# berthaBluetooth.net
KiCad netlist of a schematic drawn in EAGLE
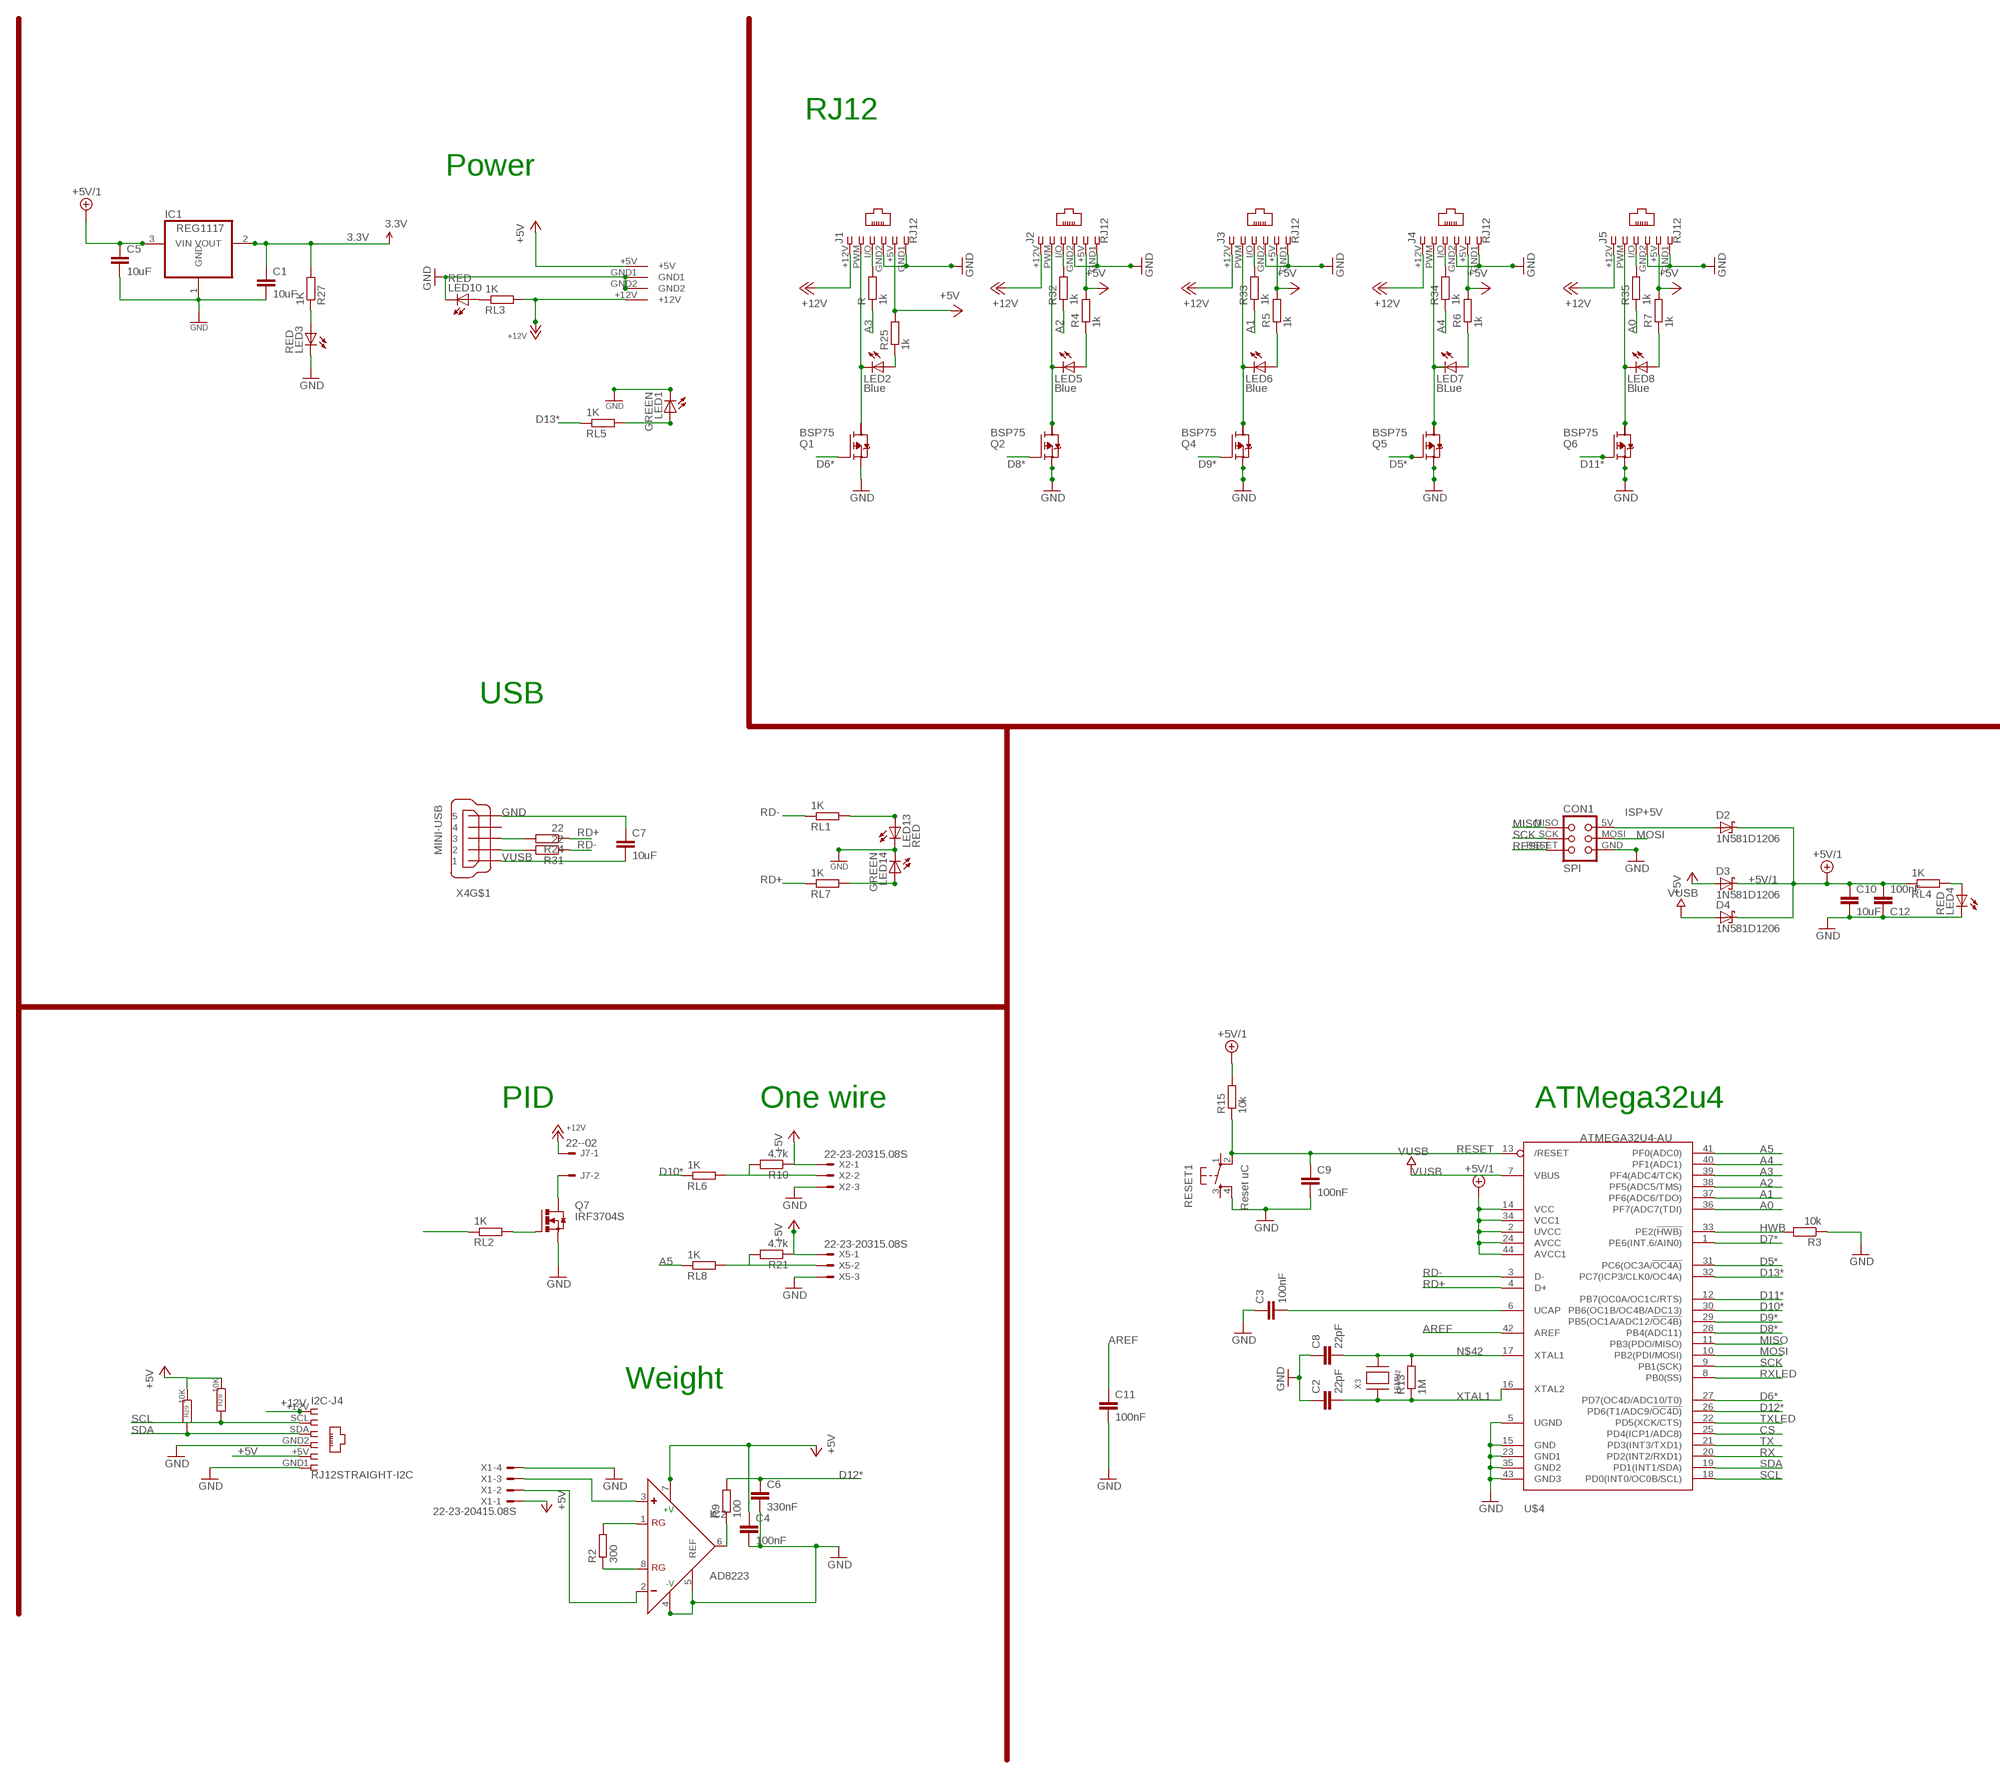
[diagram p0: schematic, sheet 1, part 1 of 2]
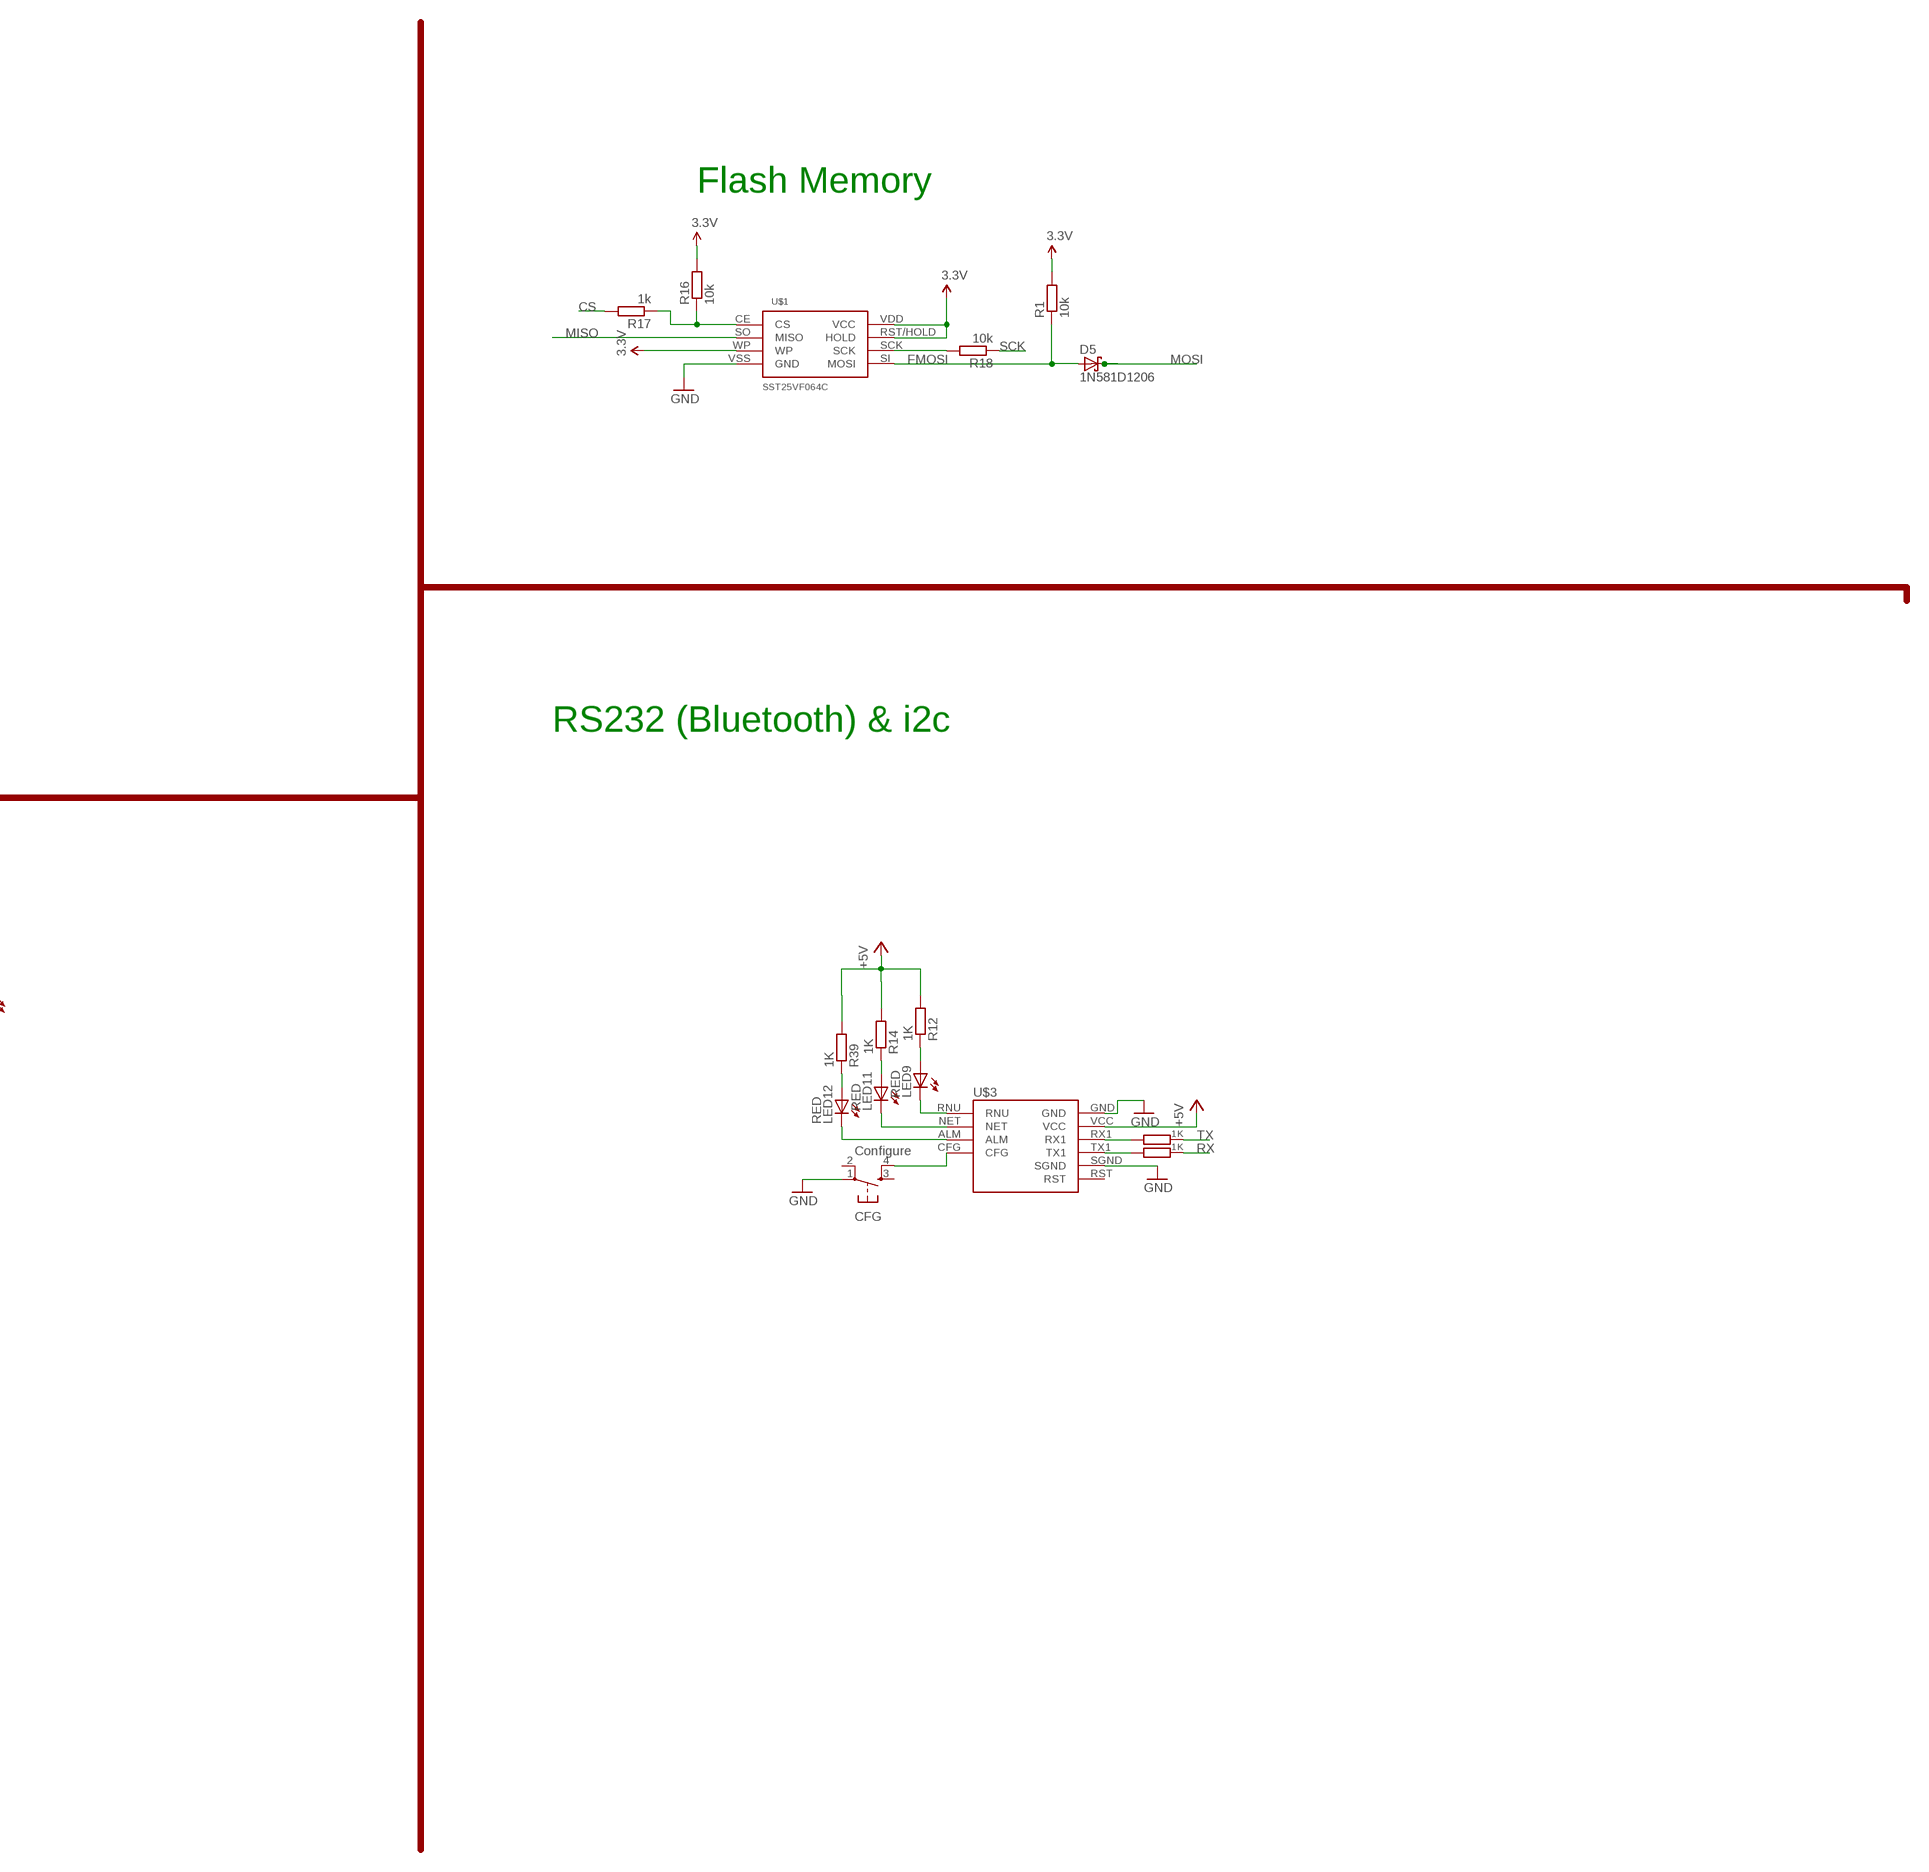
[diagram p1: schematic, sheet 1, part 2 of 2]

(export (version "E")
  (design (tool "Eeschema 10.0.6"))
  (components
    (comp (ref "C1")
      (value "10uF")
      (footprint "eagle-import:C1206")
      (libsource (lib "eagle-import") (part "C-EUC1206"))
    )
    (comp (ref "C2")
      (value "22pF")
      (footprint "eagle-import:C1206")
      (libsource (lib "eagle-import") (part "C-EUC1206"))
    )
    (comp (ref "C3")
      (value "100nF")
      (footprint "eagle-import:C1206")
      (libsource (lib "eagle-import") (part "C-EUC1206"))
    )
    (comp (ref "C4")
      (value "100nF")
      (footprint "eagle-import:C1206")
      (libsource (lib "eagle-import") (part "C-EUC1206"))
    )
    (comp (ref "C5")
      (value "10uF")
      (footprint "eagle-import:C1206")
      (libsource (lib "eagle-import") (part "C-EUC1206"))
    )
    (comp (ref "C6")
      (value "330nF")
      (footprint "eagle-import:C1206")
      (libsource (lib "eagle-import") (part "C-EUC1206"))
    )
    (comp (ref "C7")
      (value "10uF")
      (footprint "eagle-import:C1206")
      (libsource (lib "eagle-import") (part "C-EUC1206"))
    )
    (comp (ref "C8")
      (value "22pF")
      (footprint "eagle-import:C1206")
      (libsource (lib "eagle-import") (part "C-EUC1206"))
    )
    (comp (ref "C9")
      (value "100nF")
      (footprint "eagle-import:C1206")
      (libsource (lib "eagle-import") (part "C-EUC1206"))
    )
    (comp (ref "C10")
      (value "10uF")
      (footprint "eagle-import:C1206")
      (libsource (lib "eagle-import") (part "C-EUC1206"))
    )
    (comp (ref "C11")
      (value "100nF")
      (footprint "eagle-import:C1206")
      (libsource (lib "eagle-import") (part "C-EUC1206"))
    )
    (comp (ref "C12")
      (value "100nF")
      (footprint "eagle-import:C1206")
      (libsource (lib "eagle-import") (part "C-EUC1206"))
    )
    (comp (ref "CFG")
      (value "Configure")
      (footprint "eagle-import:TACTILE_SWITCH_SMD")
      (libsource (lib "eagle-import") (part "TAC_SWITCHSMD"))
    )
    (comp (ref "CON1")
      (value "SPI")
      (footprint "eagle-import:TC2030-MCP-NL")
      (libsource (lib "eagle-import") (part "TINYISPT"))
    )
    (comp (ref "D2")
      (value "1N581D1206")
      (footprint "eagle-import:LED-1206")
      (libsource (lib "eagle-import") (part "1N581D1206"))
    )
    (comp (ref "D3")
      (value "1N581D1206")
      (footprint "eagle-import:LED-1206")
      (libsource (lib "eagle-import") (part "1N581D1206"))
    )
    (comp (ref "D4")
      (value "1N581D1206")
      (footprint "eagle-import:LED-1206")
      (libsource (lib "eagle-import") (part "1N581D1206"))
    )
    (comp (ref "D5")
      (value "1N581D1206")
      (footprint "eagle-import:LED-1206")
      (libsource (lib "eagle-import") (part "1N581D1206"))
    )
    (comp (ref "I2C-J4")
      (value "RJ12STRAIGHT-I2C")
      (footprint "eagle-import:RJ12-STRAIGHT-I2C")
      (libsource (lib "eagle-import") (part "RJ12STRAIGHT-I2C"))
    )
    (comp (ref "IC1")
      (value "REG1117")
      (footprint "eagle-import:SOT223")
      (libsource (lib "eagle-import") (part "REG1117"))
    )
    (comp (ref "IC2")
      (value "AD8223")
      (footprint "eagle-import:SO8")
      (fields (field (name "MPN") "AD620AR"))
      (libsource (lib "eagle-import") (part "AD620R"))
    )
    (comp (ref "J1")
      (value "RJ12")
      (footprint "eagle-import:RJ12-STRAIGHT")
      (libsource (lib "eagle-import") (part "RJ12STRAIGHT"))
    )
    (comp (ref "J2")
      (value "RJ12")
      (footprint "eagle-import:RJ12-STRAIGHT")
      (libsource (lib "eagle-import") (part "RJ12STRAIGHT"))
    )
    (comp (ref "J3")
      (value "RJ12")
      (footprint "eagle-import:RJ12-STRAIGHT")
      (libsource (lib "eagle-import") (part "RJ12STRAIGHT"))
    )
    (comp (ref "J4")
      (value "RJ12")
      (footprint "eagle-import:RJ12-STRAIGHT")
      (libsource (lib "eagle-import") (part "RJ12STRAIGHT"))
    )
    (comp (ref "J5")
      (value "RJ12")
      (footprint "eagle-import:RJ12-STRAIGHT")
      (libsource (lib "eagle-import") (part "RJ12STRAIGHT"))
    )
    (comp (ref "J7")
      (value "22--02")
      (footprint "eagle-import:2-PIN-5.08S")
      (libsource (lib "eagle-import") (part "22-?-02"))
    )
    (comp (ref "LED1")
      (value "GREEN")
      (footprint "eagle-import:CHIPLED_1206")
      (libsource (lib "eagle-import") (part "LEDCHIPLED_1206"))
    )
    (comp (ref "LED2")
      (value "Blue")
      (footprint "eagle-import:CHIPLED_1206")
      (libsource (lib "eagle-import") (part "LEDCHIPLED_1206"))
    )
    (comp (ref "LED3")
      (value "RED")
      (footprint "eagle-import:CHIPLED_1206")
      (libsource (lib "eagle-import") (part "LEDCHIPLED_1206"))
    )
    (comp (ref "LED4")
      (value "RED")
      (footprint "eagle-import:CHIPLED_1206")
      (libsource (lib "eagle-import") (part "LEDCHIPLED_1206"))
    )
    (comp (ref "LED5")
      (value "Blue")
      (footprint "eagle-import:CHIPLED_1206")
      (libsource (lib "eagle-import") (part "LEDCHIPLED_1206"))
    )
    (comp (ref "LED6")
      (value "Blue")
      (footprint "eagle-import:CHIPLED_1206")
      (libsource (lib "eagle-import") (part "LEDCHIPLED_1206"))
    )
    (comp (ref "LED7")
      (value "BLue")
      (footprint "eagle-import:CHIPLED_1206")
      (libsource (lib "eagle-import") (part "LEDCHIPLED_1206"))
    )
    (comp (ref "LED8")
      (value "Blue")
      (footprint "eagle-import:CHIPLED_1206")
      (libsource (lib "eagle-import") (part "LEDCHIPLED_1206"))
    )
    (comp (ref "LED9")
      (value "RED")
      (footprint "eagle-import:CHIPLED_1206")
      (libsource (lib "eagle-import") (part "LEDCHIPLED_1206"))
    )
    (comp (ref "LED10")
      (value "RED")
      (footprint "eagle-import:CHIPLED_1206")
      (libsource (lib "eagle-import") (part "LEDCHIPLED_1206"))
    )
    (comp (ref "LED11")
      (value "RED")
      (footprint "eagle-import:CHIPLED_1206")
      (libsource (lib "eagle-import") (part "LEDCHIPLED_1206"))
    )
    (comp (ref "LED12")
      (value "RED")
      (footprint "eagle-import:CHIPLED_1206")
      (libsource (lib "eagle-import") (part "LEDCHIPLED_1206"))
    )
    (comp (ref "LED13")
      (value "RED")
      (footprint "eagle-import:CHIPLED_1206")
      (libsource (lib "eagle-import") (part "LEDCHIPLED_1206"))
    )
    (comp (ref "LED14")
      (value "GREEN")
      (footprint "eagle-import:CHIPLED_1206")
      (libsource (lib "eagle-import") (part "LEDCHIPLED_1206"))
    )
    (comp (ref "Q1")
      (value "BSP75")
      (footprint "eagle-import:PG-SOT-223")
      (libsource (lib "eagle-import") (part "BSP613P"))
    )
    (comp (ref "Q2")
      (value "BSP75")
      (footprint "eagle-import:PG-SOT-223")
      (libsource (lib "eagle-import") (part "BSP613P"))
    )
    (comp (ref "Q4")
      (value "BSP75")
      (footprint "eagle-import:PG-SOT-223")
      (libsource (lib "eagle-import") (part "BSP613P"))
    )
    (comp (ref "Q5")
      (value "BSP75")
      (footprint "eagle-import:PG-SOT-223")
      (libsource (lib "eagle-import") (part "BSP613P"))
    )
    (comp (ref "Q6")
      (value "BSP75")
      (footprint "eagle-import:PG-SOT-223")
      (libsource (lib "eagle-import") (part "BSP613P"))
    )
    (comp (ref "Q7")
      (value "IRF3704S")
      (footprint "eagle-import:D2PACK")
      (libsource (lib "eagle-import") (part "IRF3704S"))
    )
    (comp (ref "R")
      (value "1k")
      (footprint "eagle-import:R0805")
      (libsource (lib "eagle-import") (part "R-EU_R0805"))
    )
    (comp (ref "R1")
      (value "10k")
      (footprint "eagle-import:R0805")
      (libsource (lib "eagle-import") (part "R-EU_R0805"))
    )
    (comp (ref "R2")
      (value "300")
      (footprint "eagle-import:R1206")
      (libsource (lib "eagle-import") (part "resistor_R-EU_R1206"))
    )
    (comp (ref "R3")
      (value "10k")
      (footprint "eagle-import:M0805")
      (libsource (lib "eagle-import") (part "resistor_R-EU_M0805"))
    )
    (comp (ref "R4")
      (value "1k")
      (footprint "eagle-import:R0805")
      (libsource (lib "eagle-import") (part "R-EU_R0805"))
    )
    (comp (ref "R5")
      (value "1k")
      (footprint "eagle-import:R0805")
      (libsource (lib "eagle-import") (part "R-EU_R0805"))
    )
    (comp (ref "R6")
      (value "1k")
      (footprint "eagle-import:R0805")
      (libsource (lib "eagle-import") (part "R-EU_R0805"))
    )
    (comp (ref "R7")
      (value "1k")
      (footprint "eagle-import:R0805")
      (libsource (lib "eagle-import") (part "R-EU_R0805"))
    )
    (comp (ref "R8")
      (value "1K")
      (footprint "eagle-import:R0805")
      (libsource (lib "eagle-import") (part "R-EU_R0805"))
    )
    (comp (ref "R9")
      (value "100")
      (footprint "eagle-import:R1206")
      (libsource (lib "eagle-import") (part "resistor_R-EU_R1206"))
    )
    (comp (ref "R10")
      (value "4.7k")
      (footprint "eagle-import:R1206")
      (libsource (lib "eagle-import") (part "resistor_R-EU_R1206"))
    )
    (comp (ref "R11")
      (value "1K")
      (footprint "eagle-import:R0805")
      (libsource (lib "eagle-import") (part "R-EU_R0805"))
    )
    (comp (ref "R12")
      (value "1K")
      (footprint "eagle-import:R0805")
      (libsource (lib "eagle-import") (part "R-EU_R0805"))
    )
    (comp (ref "R13")
      (value "1M")
      (footprint "eagle-import:R1206")
      (libsource (lib "eagle-import") (part "R-EU_R1206"))
    )
    (comp (ref "R14")
      (value "1K")
      (footprint "eagle-import:R0805")
      (libsource (lib "eagle-import") (part "R-EU_R0805"))
    )
    (comp (ref "R15")
      (value "10k")
      (footprint "eagle-import:M0805")
      (libsource (lib "eagle-import") (part "resistor_R-EU_M0805"))
    )
    (comp (ref "R16")
      (value "10k")
      (footprint "eagle-import:R0805")
      (libsource (lib "eagle-import") (part "R-EU_R0805"))
    )
    (comp (ref "R17")
      (value "1k")
      (footprint "eagle-import:R0805")
      (libsource (lib "eagle-import") (part "R-EU_R0805"))
    )
    (comp (ref "R18")
      (value "10k")
      (footprint "eagle-import:R0805")
      (libsource (lib "eagle-import") (part "R-EU_R0805"))
    )
    (comp (ref "R21")
      (value "4.7k")
      (footprint "eagle-import:R1206")
      (libsource (lib "eagle-import") (part "resistor_R-EU_R1206"))
    )
    (comp (ref "R24")
      (value "22")
      (footprint "eagle-import:M1206")
      (libsource (lib "eagle-import") (part "resistor_R-EU_M1206"))
    )
    (comp (ref "R25")
      (value "1k")
      (footprint "eagle-import:R0805")
      (libsource (lib "eagle-import") (part "R-EU_R0805"))
    )
    (comp (ref "R27")
      (value "1K")
      (footprint "eagle-import:R0805")
      (libsource (lib "eagle-import") (part "R-EU_R0805"))
    )
    (comp (ref "R28")
      (value "10K")
      (footprint "eagle-import:M0805")
      (libsource (lib "eagle-import") (part "resistor_R-EU_M0805"))
    )
    (comp (ref "R29")
      (value "10K")
      (footprint "eagle-import:M0805")
      (libsource (lib "eagle-import") (part "resistor_R-EU_M0805"))
    )
    (comp (ref "R31")
      (value "22")
      (footprint "eagle-import:M1206")
      (libsource (lib "eagle-import") (part "resistor_R-EU_M1206"))
    )
    (comp (ref "R32")
      (value "1k")
      (footprint "eagle-import:R0805")
      (libsource (lib "eagle-import") (part "R-EU_R0805"))
    )
    (comp (ref "R33")
      (value "1k")
      (footprint "eagle-import:R0805")
      (libsource (lib "eagle-import") (part "R-EU_R0805"))
    )
    (comp (ref "R34")
      (value "1k")
      (footprint "eagle-import:R0805")
      (libsource (lib "eagle-import") (part "R-EU_R0805"))
    )
    (comp (ref "R35")
      (value "1k")
      (footprint "eagle-import:R0805")
      (libsource (lib "eagle-import") (part "R-EU_R0805"))
    )
    (comp (ref "R39")
      (value "1K")
      (footprint "eagle-import:R0805")
      (libsource (lib "eagle-import") (part "R-EU_R0805"))
    )
    (comp (ref "RESET1")
      (value "Reset uC")
      (footprint "eagle-import:TACTILE_SWITCH_SMD")
      (libsource (lib "eagle-import") (part "TAC_SWITCHSMD"))
    )
    (comp (ref "RL1")
      (value "1K")
      (footprint "eagle-import:R0805")
      (libsource (lib "eagle-import") (part "R-EU_R0805"))
    )
    (comp (ref "RL2")
      (value "1K")
      (footprint "eagle-import:R0805")
      (libsource (lib "eagle-import") (part "R-EU_R0805"))
    )
    (comp (ref "RL3")
      (value "1K")
      (footprint "eagle-import:R0805")
      (libsource (lib "eagle-import") (part "R-EU_R0805"))
    )
    (comp (ref "RL4")
      (value "1K")
      (footprint "eagle-import:R0805")
      (libsource (lib "eagle-import") (part "resistor_R-EU_R0805"))
    )
    (comp (ref "RL5")
      (value "1K")
      (footprint "eagle-import:R0805")
      (libsource (lib "eagle-import") (part "R-EU_R0805"))
    )
    (comp (ref "RL6")
      (value "1K")
      (footprint "eagle-import:R0805")
      (libsource (lib "eagle-import") (part "R-EU_R0805"))
    )
    (comp (ref "RL7")
      (value "1K")
      (footprint "eagle-import:R0805")
      (libsource (lib "eagle-import") (part "R-EU_R0805"))
    )
    (comp (ref "RL8")
      (value "1K")
      (footprint "eagle-import:R0805")
      (libsource (lib "eagle-import") (part "R-EU_R0805"))
    )
    (comp (ref "U$1")
      (value "SST25VF064C")
      (footprint "eagle-import:SOIC_8-LEAD")
      (libsource (lib "eagle-import") (part "SST25VF064C"))
    )
    (comp (ref "U$3")
      (value "SZ05-ZIGBEE")
      (footprint "eagle-import:SZ05-ZIGBEE")
      (libsource (lib "eagle-import") (part "SZ05-ZIGBEE"))
    )
    (comp (ref "U$4")
      (value "ATMEGA32U4-AU")
      (footprint "eagle-import:TQFP44")
      (libsource (lib "eagle-import") (part "ATMEGA32U4-AU"))
    )
    (comp (ref "U$6")
      (value "KPJX-4S-S")
      (footprint "eagle-import:KPJX-4S-S")
      (libsource (lib "eagle-import") (part "KPJX-4S-S"))
    )
    (comp (ref "X1")
      (value "22-23-20415.08S")
      (footprint "eagle-import:4-PIN-5.08S")
      (libsource (lib "eagle-import") (part "22-23-20415.08S"))
    )
    (comp (ref "X2")
      (value "22-23-20315.08S")
      (footprint "eagle-import:3-PIN-5.08S")
      (libsource (lib "eagle-import") (part "22-23-20315.08S"))
    )
    (comp (ref "X3")
      (value "16MHz")
      (footprint "eagle-import:NX6035")
      (libsource (lib "eagle-import") (part "XTALNX6035"))
    )
    (comp (ref "X4")
      (value "MINI-USB")
      (footprint "eagle-import:32005-201")
      (libsource (lib "eagle-import") (part "MINI-USB-SCHIELD-32005-201"))
    )
    (comp (ref "X5")
      (value "22-23-20315.08S")
      (footprint "eagle-import:3-PIN-5.08S")
      (libsource (lib "eagle-import") (part "22-23-20315.08S"))
    )
  )
  (nets
    (net (code "1") (name "+5V") (class "Default")
      (node (ref "C4") (pin "1") (pinfunction "1_1") (pintype "passive"))
      (node (ref "D3") (pin "A") (pinfunction "A_A") (pintype "passive"))
      (node (ref "I2C-J4") (pin "+5V") (pinfunction "5_+5V") (pintype "bidirectional"))
      (node (ref "IC2") (pin "7") (pinfunction "+V_7") (pintype "power_in"))
      (node (ref "J1") (pin "+5V") (pinfunction "5_+5V") (pintype "bidirectional"))
      (node (ref "J2") (pin "+5V") (pinfunction "5_+5V") (pintype "bidirectional"))
      (node (ref "J3") (pin "+5V") (pinfunction "5_+5V") (pintype "bidirectional"))
      (node (ref "J4") (pin "+5V") (pinfunction "5_+5V") (pintype "bidirectional"))
      (node (ref "J5") (pin "+5V") (pinfunction "5_+5V") (pintype "bidirectional"))
      (node (ref "R10") (pin "1") (pinfunction "1_1") (pintype "passive"))
      (node (ref "R12") (pin "2") (pinfunction "2_2") (pintype "passive"))
      (node (ref "R14") (pin "2") (pinfunction "2_2") (pintype "passive"))
      (node (ref "R21") (pin "1") (pinfunction "1_1") (pintype "passive"))
      (node (ref "R25") (pin "2") (pinfunction "2_2") (pintype "passive"))
      (node (ref "R28") (pin "1") (pinfunction "1_1") (pintype "passive"))
      (node (ref "R29") (pin "1") (pinfunction "1_1") (pintype "passive"))
      (node (ref "R39") (pin "2") (pinfunction "2_2") (pintype "passive"))
      (node (ref "R4") (pin "2") (pinfunction "2_2") (pintype "passive"))
      (node (ref "R5") (pin "2") (pinfunction "2_2") (pintype "passive"))
      (node (ref "R6") (pin "2") (pinfunction "2_2") (pintype "passive"))
      (node (ref "R7") (pin "2") (pinfunction "2_2") (pintype "passive"))
      (node (ref "U$3") (pin "VCC") (pinfunction "VCC_VCC") (pintype "bidirectional"))
      (node (ref "U$6") (pin "+5V") (pinfunction "+5V_+5V") (pintype "power_in"))
      (node (ref "X1") (pin "1") (pinfunction "S_1") (pintype "passive"))
      (node (ref "X2") (pin "1") (pinfunction "S_1") (pintype "passive"))
      (node (ref "X5") (pin "1") (pinfunction "S_1") (pintype "passive"))
    )
    (net (code "2") (name "+5V{slash}1") (class "Default")
      (node (ref "C10") (pin "1") (pinfunction "1_1") (pintype "passive"))
      (node (ref "C12") (pin "2") (pinfunction "2_2") (pintype "passive"))
      (node (ref "C5") (pin "1") (pinfunction "1_1") (pintype "passive"))
      (node (ref "D2") (pin "C") (pinfunction "C_C") (pintype "passive"))
      (node (ref "D3") (pin "C") (pinfunction "C_C") (pintype "passive"))
      (node (ref "D4") (pin "C") (pinfunction "C_C") (pintype "passive"))
      (node (ref "IC1") (pin "3") (pinfunction "VIN_3") (pintype "input"))
      (node (ref "R15") (pin "2") (pinfunction "2_2") (pintype "passive"))
      (node (ref "RL4") (pin "1") (pinfunction "1_1") (pintype "passive"))
      (node (ref "U$4") (pin "14") (pinfunction "VCC_14") (pintype "bidirectional"))
      (node (ref "U$4") (pin "2") (pinfunction "UVCC_2") (pintype "bidirectional"))
      (node (ref "U$4") (pin "24") (pinfunction "AVCC_24") (pintype "bidirectional"))
      (node (ref "U$4") (pin "34") (pinfunction "VCC1_34") (pintype "bidirectional"))
      (node (ref "U$4") (pin "44") (pinfunction "AVCC1_44") (pintype "bidirectional"))
    )
    (net (code "3") (name "+12V") (class "Default")
      (node (ref "I2C-J4") (pin "+12V") (pinfunction "1_+12V") (pintype "bidirectional"))
      (node (ref "J1") (pin "+12V") (pinfunction "1_+12V") (pintype "bidirectional"))
      (node (ref "J2") (pin "+12V") (pinfunction "1_+12V") (pintype "bidirectional"))
      (node (ref "J3") (pin "+12V") (pinfunction "1_+12V") (pintype "bidirectional"))
      (node (ref "J4") (pin "+12V") (pinfunction "1_+12V") (pintype "bidirectional"))
      (node (ref "J5") (pin "+12V") (pinfunction "1_+12V") (pintype "bidirectional"))
      (node (ref "J7") (pin "1") (pinfunction "S_1") (pintype "passive"))
      (node (ref "RL3") (pin "2") (pinfunction "2_2") (pintype "passive"))
      (node (ref "U$6") (pin "+12V") (pinfunction "+12V_+12V") (pintype "power_in"))
    )
    (net (code "4") (name "/A0") (class "Default")
      (node (ref "R35") (pin "1") (pinfunction "1_1") (pintype "passive"))
      (node (ref "U$4") (pin "36") (pinfunction "PF7(ADC7(TDI)_36") (pintype "bidirectional"))
    )
    (net (code "5") (name "/A1") (class "Default")
      (node (ref "R33") (pin "1") (pinfunction "1_1") (pintype "passive"))
      (node (ref "U$4") (pin "37") (pinfunction "PF6(ADC6/TDO)_37") (pintype "bidirectional"))
    )
    (net (code "6") (name "/A2") (class "Default")
      (node (ref "R32") (pin "1") (pinfunction "1_1") (pintype "passive"))
      (node (ref "U$4") (pin "38") (pinfunction "PF5(ADC5/TMS)_38") (pintype "bidirectional"))
    )
    (net (code "7") (name "/A3") (class "Default")
      (node (ref "R") (pin "1") (pinfunction "1_1") (pintype "passive"))
      (node (ref "U$4") (pin "39") (pinfunction "PF4(ADC4/TCK)_39") (pintype "bidirectional"))
    )
    (net (code "8") (name "/A4") (class "Default")
      (node (ref "R34") (pin "1") (pinfunction "1_1") (pintype "passive"))
      (node (ref "U$4") (pin "40") (pinfunction "PF1(ADC1)_40") (pintype "bidirectional"))
    )
    (net (code "9") (name "/A5") (class "Default")
      (node (ref "RL8") (pin "1") (pinfunction "1_1") (pintype "passive"))
      (node (ref "U$4") (pin "41") (pinfunction "PF0(ADC0)_41") (pintype "bidirectional"))
    )
    (net (code "10") (name "/AREF") (class "Default")
      (node (ref "C11") (pin "1") (pinfunction "1_1") (pintype "passive"))
      (node (ref "U$4") (pin "42") (pinfunction "AREF_42") (pintype "bidirectional"))
    )
    (net (code "11") (name "/CS") (class "Default")
      (node (ref "R17") (pin "2") (pinfunction "2_2") (pintype "passive"))
      (node (ref "U$4") (pin "25") (pinfunction "PD4(ICP1/ADC8)_25") (pintype "bidirectional"))
    )
    (net (code "12") (name "/D5*") (class "Default")
      (node (ref "Q5") (pin "1") (pinfunction "G_1") (pintype "passive"))
      (node (ref "U$4") (pin "31") (pinfunction "PC6(OC3A/~{OC4A})_31") (pintype "bidirectional"))
    )
    (net (code "13") (name "/D6*") (class "Default")
      (node (ref "Q1") (pin "1") (pinfunction "G_1") (pintype "passive"))
      (node (ref "U$4") (pin "27") (pinfunction "PD7(OC4D/ADC10/T0)_27") (pintype "bidirectional"))
    )
    (net (code "14") (name "/D7*") (class "Default")
      (node (ref "RL2") (pin "1") (pinfunction "1_1") (pintype "passive"))
      (node (ref "U$4") (pin "1") (pinfunction "PE6(INT.6/AIN0)_1") (pintype "bidirectional"))
    )
    (net (code "15") (name "/D8*") (class "Default")
      (node (ref "Q2") (pin "1") (pinfunction "G_1") (pintype "passive"))
      (node (ref "U$4") (pin "28") (pinfunction "PB4(ADC11)_28") (pintype "bidirectional"))
    )
    (net (code "16") (name "/D9*") (class "Default")
      (node (ref "Q4") (pin "1") (pinfunction "G_1") (pintype "passive"))
      (node (ref "U$4") (pin "29") (pinfunction "PB5(OC1A/ADC12/~{OC4B})_29") (pintype "bidirectional"))
    )
    (net (code "17") (name "/D10*") (class "Default")
      (node (ref "RL6") (pin "1") (pinfunction "1_1") (pintype "passive"))
      (node (ref "U$4") (pin "30") (pinfunction "PB6(OC1B/OC4B/ADC13)_30") (pintype "bidirectional"))
    )
    (net (code "18") (name "/D11*") (class "Default")
      (node (ref "Q6") (pin "1") (pinfunction "G_1") (pintype "passive"))
      (node (ref "U$4") (pin "12") (pinfunction "PB7(OC0A/OC1C/RTS)_12") (pintype "bidirectional"))
    )
    (net (code "19") (name "/D12*") (class "Default")
      (node (ref "C6") (pin "1") (pinfunction "1_1") (pintype "passive"))
      (node (ref "R9") (pin "2") (pinfunction "2_2") (pintype "passive"))
      (node (ref "U$4") (pin "26") (pinfunction "PD6(T1/ADC9/~{OC4D})_26") (pintype "bidirectional"))
    )
    (net (code "20") (name "/D13*") (class "Default")
      (node (ref "RL5") (pin "1") (pinfunction "1_1") (pintype "passive"))
      (node (ref "U$4") (pin "32") (pinfunction "PC7(ICP3/CLK0/OC4A)_32") (pintype "bidirectional"))
    )
    (net (code "21") (name "/FMOSI") (class "Default")
      (node (ref "D5") (pin "A") (pinfunction "A_A") (pintype "passive"))
      (node (ref "R1") (pin "1") (pinfunction "1_1") (pintype "passive"))
      (node (ref "U$1") (pin "SI") (pinfunction "MOSI_SI") (pintype "bidirectional"))
    )
    (net (code "22") (name "/HWB") (class "Default")
      (node (ref "R3") (pin "2") (pinfunction "2_2") (pintype "passive"))
      (node (ref "U$4") (pin "33") (pinfunction "PE2(~{HWB})_33") (pintype "bidirectional"))
    )
    (net (code "23") (name "/ISP+5V") (class "Default")
      (node (ref "CON1") (pin "5V") (pinfunction "VCC_5V") (pintype "passive"))
      (node (ref "D2") (pin "A") (pinfunction "A_A") (pintype "passive"))
    )
    (net (code "24") (name "/MISO") (class "Default")
      (node (ref "CON1") (pin "MISO") (pinfunction "MISO_MISO") (pintype "passive"))
      (node (ref "U$1") (pin "SO") (pinfunction "MISO_SO") (pintype "bidirectional"))
      (node (ref "U$4") (pin "11") (pinfunction "PB3(PDO/MISO)_11") (pintype "bidirectional"))
    )
    (net (code "25") (name "/MOSI") (class "Default")
      (node (ref "CON1") (pin "MOSI") (pinfunction "MOSI_MOSI") (pintype "passive"))
      (node (ref "D5") (pin "C") (pinfunction "C_C") (pintype "passive"))
      (node (ref "U$4") (pin "10") (pinfunction "PB2(PDI/MOSI)_10") (pintype "bidirectional"))
    )
    (net (code "26") (name "/N$42") (class "Default")
      (node (ref "C8") (pin "2") (pinfunction "2_2") (pintype "passive"))
      (node (ref "R13") (pin "2") (pinfunction "2_2") (pintype "passive"))
      (node (ref "U$4") (pin "17") (pinfunction "XTAL1_17") (pintype "bidirectional"))
      (node (ref "X3") (pin "P$2") (pinfunction "P$2_P$2") (pintype "bidirectional"))
    )
    (net (code "27") (name "/RD+") (class "Default")
      (node (ref "R24") (pin "1") (pinfunction "1_1") (pintype "passive"))
      (node (ref "RL7") (pin "1") (pinfunction "1_1") (pintype "passive"))
      (node (ref "U$4") (pin "4") (pinfunction "D+_4") (pintype "bidirectional"))
    )
    (net (code "28") (name "/RD-") (class "Default")
      (node (ref "R31") (pin "1") (pinfunction "1_1") (pintype "passive"))
      (node (ref "RL1") (pin "1") (pinfunction "1_1") (pintype "passive"))
      (node (ref "U$4") (pin "3") (pinfunction "D-_3") (pintype "bidirectional"))
    )
    (net (code "29") (name "/RESET") (class "Default")
      (node (ref "C9") (pin "1") (pinfunction "1_1") (pintype "passive"))
      (node (ref "CON1") (pin "RESET") (pinfunction "RESET_RESET") (pintype "passive"))
      (node (ref "R15") (pin "1") (pinfunction "1_1") (pintype "passive"))
      (node (ref "RESET1") (pin "2") (pinfunction "2_2") (pintype "passive"))
      (node (ref "U$4") (pin "13") (pinfunction "/RESET_13") (pintype "bidirectional"))
    )
    (net (code "30") (name "/RX") (class "Default")
      (node (ref "R8") (pin "1") (pinfunction "1_1") (pintype "passive"))
      (node (ref "U$4") (pin "20") (pinfunction "PD2(INT2/RXD1)_20") (pintype "bidirectional"))
    )
    (net (code "31") (name "/RXLED") (class "Default")
      (node (ref "U$4") (pin "8") (pinfunction "PB0(SS)_8") (pintype "bidirectional"))
    )
    (net (code "32") (name "/SCK") (class "Default")
      (node (ref "CON1") (pin "SCK") (pinfunction "SCK_SCK") (pintype "passive"))
      (node (ref "R18") (pin "1") (pinfunction "1_1") (pintype "passive"))
      (node (ref "U$4") (pin "9") (pinfunction "PB1(SCK)_9") (pintype "bidirectional"))
    )
    (net (code "33") (name "/SCL") (class "Default")
      (node (ref "I2C-J4") (pin "SCL") (pinfunction "2_SCL") (pintype "bidirectional"))
      (node (ref "R28") (pin "2") (pinfunction "2_2") (pintype "passive"))
      (node (ref "U$4") (pin "18") (pinfunction "PD0(INT0/OC0B/SCL)_18") (pintype "bidirectional"))
    )
    (net (code "34") (name "/SDA") (class "Default")
      (node (ref "I2C-J4") (pin "SDA") (pinfunction "3_SDA") (pintype "bidirectional"))
      (node (ref "R29") (pin "2") (pinfunction "2_2") (pintype "passive"))
      (node (ref "U$4") (pin "19") (pinfunction "PD1(INT1/SDA)_19") (pintype "bidirectional"))
    )
    (net (code "35") (name "/TX") (class "Default")
      (node (ref "R11") (pin "1") (pinfunction "1_1") (pintype "passive"))
      (node (ref "U$4") (pin "21") (pinfunction "PD3(INT3/TXD1)_21") (pintype "bidirectional"))
    )
    (net (code "36") (name "/TXLED") (class "Default")
      (node (ref "U$4") (pin "22") (pinfunction "PD5(XCK/CTS)_22") (pintype "bidirectional"))
    )
    (net (code "37") (name "/XTAL1") (class "Default")
      (node (ref "C2") (pin "2") (pinfunction "2_2") (pintype "passive"))
      (node (ref "R13") (pin "1") (pinfunction "1_1") (pintype "passive"))
      (node (ref "U$4") (pin "16") (pinfunction "XTAL2_16") (pintype "bidirectional"))
      (node (ref "X3") (pin "P$1") (pinfunction "P$1_P$1") (pintype "bidirectional"))
    )
    (net (code "38") (name "3.3V") (class "Default")
      (node (ref "C1") (pin "1") (pinfunction "1_1") (pintype "passive"))
      (node (ref "IC1") (pin "2") (pinfunction "VOUT_2") (pintype "output"))
      (node (ref "R1") (pin "2") (pinfunction "2_2") (pintype "passive"))
      (node (ref "R16") (pin "2") (pinfunction "2_2") (pintype "passive"))
      (node (ref "R27") (pin "2") (pinfunction "2_2") (pintype "passive"))
      (node (ref "U$1") (pin "RST/HOLD") (pinfunction "HOLD_RST/HOLD") (pintype "bidirectional"))
      (node (ref "U$1") (pin "VDD") (pinfunction "VCC_VDD") (pintype "bidirectional"))
      (node (ref "U$1") (pin "WP") (pinfunction "WP_WP") (pintype "bidirectional"))
    )
    (net (code "39") (name "GND") (class "Default")
      (node (ref "C1") (pin "2") (pinfunction "2_2") (pintype "passive"))
      (node (ref "C10") (pin "2") (pinfunction "2_2") (pintype "passive"))
      (node (ref "C11") (pin "2") (pinfunction "2_2") (pintype "passive"))
      (node (ref "C12") (pin "1") (pinfunction "1_1") (pintype "passive"))
      (node (ref "C2") (pin "1") (pinfunction "1_1") (pintype "passive"))
      (node (ref "C3") (pin "1") (pinfunction "1_1") (pintype "passive"))
      (node (ref "C4") (pin "2") (pinfunction "2_2") (pintype "passive"))
      (node (ref "C5") (pin "2") (pinfunction "2_2") (pintype "passive"))
      (node (ref "C6") (pin "2") (pinfunction "2_2") (pintype "passive"))
      (node (ref "C7") (pin "1") (pinfunction "1_1") (pintype "passive"))
      (node (ref "C8") (pin "1") (pinfunction "1_1") (pintype "passive"))
      (node (ref "C9") (pin "2") (pinfunction "2_2") (pintype "passive"))
      (node (ref "CFG") (pin "1") (pinfunction "1_1") (pintype "passive"))
      (node (ref "CON1") (pin "GND") (pinfunction "GND_GND") (pintype "passive"))
      (node (ref "I2C-J4") (pin "GND1") (pinfunction "6_GND1") (pintype "bidirectional"))
      (node (ref "I2C-J4") (pin "GND2") (pinfunction "4_GND2") (pintype "bidirectional"))
      (node (ref "IC1") (pin "1") (pinfunction "GND_1") (pintype "power_in"))
      (node (ref "IC2") (pin "4") (pinfunction "-V_4") (pintype "power_in"))
      (node (ref "IC2") (pin "5") (pinfunction "REF_5") (pintype "passive"))
      (node (ref "J1") (pin "GND1") (pinfunction "6_GND1") (pintype "bidirectional"))
      (node (ref "J1") (pin "GND2") (pinfunction "4_GND2") (pintype "bidirectional"))
      (node (ref "J2") (pin "GND1") (pinfunction "6_GND1") (pintype "bidirectional"))
      (node (ref "J2") (pin "GND2") (pinfunction "4_GND2") (pintype "bidirectional"))
      (node (ref "J3") (pin "GND1") (pinfunction "6_GND1") (pintype "bidirectional"))
      (node (ref "J3") (pin "GND2") (pinfunction "4_GND2") (pintype "bidirectional"))
      (node (ref "J4") (pin "GND1") (pinfunction "6_GND1") (pintype "bidirectional"))
      (node (ref "J4") (pin "GND2") (pinfunction "4_GND2") (pintype "bidirectional"))
      (node (ref "J5") (pin "GND1") (pinfunction "6_GND1") (pintype "bidirectional"))
      (node (ref "J5") (pin "GND2") (pinfunction "4_GND2") (pintype "bidirectional"))
      (node (ref "LED1") (pin "C") (pinfunction "C_C") (pintype "passive"))
      (node (ref "LED10") (pin "C") (pinfunction "C_C") (pintype "passive"))
      (node (ref "LED13") (pin "C") (pinfunction "C_C") (pintype "passive"))
      (node (ref "LED14") (pin "C") (pinfunction "C_C") (pintype "passive"))
      (node (ref "LED3") (pin "C") (pinfunction "C_C") (pintype "passive"))
      (node (ref "LED4") (pin "C") (pinfunction "C_C") (pintype "passive"))
      (node (ref "Q1") (pin "3") (pinfunction "S_3") (pintype "passive"))
      (node (ref "Q2") (pin "3") (pinfunction "S_3") (pintype "passive"))
      (node (ref "Q4") (pin "3") (pinfunction "S_3") (pintype "passive"))
      (node (ref "Q5") (pin "3") (pinfunction "S_3") (pintype "passive"))
      (node (ref "Q6") (pin "3") (pinfunction "S_3") (pintype "passive"))
      (node (ref "Q7") (pin "3") (pinfunction "S_3") (pintype "passive"))
      (node (ref "R3") (pin "1") (pinfunction "1_1") (pintype "passive"))
      (node (ref "RESET1") (pin "4") (pinfunction "4_4") (pintype "passive"))
      (node (ref "U$1") (pin "VSS") (pinfunction "GND_VSS") (pintype "bidirectional"))
      (node (ref "U$3") (pin "GND") (pinfunction "GND_GND") (pintype "bidirectional"))
      (node (ref "U$3") (pin "SGND") (pinfunction "SGND_SGND") (pintype "bidirectional"))
      (node (ref "U$4") (pin "15") (pinfunction "GND_15") (pintype "bidirectional"))
      (node (ref "U$4") (pin "23") (pinfunction "GND1_23") (pintype "bidirectional"))
      (node (ref "U$4") (pin "35") (pinfunction "GND2_35") (pintype "bidirectional"))
      (node (ref "U$4") (pin "43") (pinfunction "GND3_43") (pintype "bidirectional"))
      (node (ref "U$4") (pin "5") (pinfunction "UGND_5") (pintype "bidirectional"))
      (node (ref "U$6") (pin "GND1") (pinfunction "GND1_GND1") (pintype "input"))
      (node (ref "U$6") (pin "GND2") (pinfunction "GND2_GND2") (pintype "input"))
      (node (ref "X1") (pin "4") (pinfunction "S_4") (pintype "passive"))
      (node (ref "X2") (pin "3") (pinfunction "S_3") (pintype "passive"))
      (node (ref "X4") (pin "5") (pinfunction "5_5") (pintype "passive"))
      (node (ref "X5") (pin "3") (pinfunction "S_3") (pintype "passive"))
    )
    (net (code "40") (name "Net-(CFG-Pad4)") (class "Default")
      (node (ref "CFG") (pin "4") (pinfunction "4_4") (pintype "passive"))
      (node (ref "U$3") (pin "CFG") (pinfunction "CFG_CFG") (pintype "bidirectional"))
    )
    (net (code "41") (name "Net-(IC2-+)") (class "Default")
      (node (ref "IC2") (pin "3") (pinfunction "+_3") (pintype "input"))
      (node (ref "X1") (pin "3") (pinfunction "S_3") (pintype "passive"))
    )
    (net (code "42") (name "Net-(IC2--)") (class "Default")
      (node (ref "IC2") (pin "2") (pinfunction "-_2") (pintype "input"))
      (node (ref "X1") (pin "2") (pinfunction "S_2") (pintype "passive"))
    )
    (net (code "43") (name "Net-(IC2-OUT)") (class "Default")
      (node (ref "IC2") (pin "6") (pinfunction "OUT_6") (pintype "output"))
      (node (ref "R9") (pin "1") (pinfunction "1_1") (pintype "passive"))
    )
    (net (code "44") (name "Net-(IC2-RG-Pad1)") (class "Default")
      (node (ref "IC2") (pin "1") (pinfunction "RG_1") (pintype "passive"))
      (node (ref "R2") (pin "2") (pinfunction "2_2") (pintype "passive"))
    )
    (net (code "45") (name "Net-(IC2-RG-Pad8)") (class "Default")
      (node (ref "IC2") (pin "8") (pinfunction "RG_8") (pintype "passive"))
      (node (ref "R2") (pin "1") (pinfunction "1_1") (pintype "passive"))
    )
    (net (code "46") (name "Net-(J1-2)") (class "Default")
      (node (ref "J1") (pin "PWM") (pinfunction "2_PWM") (pintype "bidirectional"))
      (node (ref "LED2") (pin "C") (pinfunction "C_C") (pintype "passive"))
      (node (ref "Q1") (pin "2") (pinfunction "D_2") (pintype "passive"))
    )
    (net (code "47") (name "Net-(J1-3)") (class "Default")
      (node (ref "J1") (pin "I/O") (pinfunction "3_I/O") (pintype "bidirectional"))
      (node (ref "R") (pin "2") (pinfunction "2_2") (pintype "passive"))
    )
    (net (code "48") (name "Net-(J2-2)") (class "Default")
      (node (ref "J2") (pin "PWM") (pinfunction "2_PWM") (pintype "bidirectional"))
      (node (ref "LED5") (pin "C") (pinfunction "C_C") (pintype "passive"))
      (node (ref "Q2") (pin "2") (pinfunction "D_2") (pintype "passive"))
    )
    (net (code "49") (name "Net-(J2-3)") (class "Default")
      (node (ref "J2") (pin "I/O") (pinfunction "3_I/O") (pintype "bidirectional"))
      (node (ref "R32") (pin "2") (pinfunction "2_2") (pintype "passive"))
    )
    (net (code "50") (name "Net-(J3-2)") (class "Default")
      (node (ref "J3") (pin "PWM") (pinfunction "2_PWM") (pintype "bidirectional"))
      (node (ref "LED6") (pin "C") (pinfunction "C_C") (pintype "passive"))
      (node (ref "Q4") (pin "2") (pinfunction "D_2") (pintype "passive"))
    )
    (net (code "51") (name "Net-(J3-3)") (class "Default")
      (node (ref "J3") (pin "I/O") (pinfunction "3_I/O") (pintype "bidirectional"))
      (node (ref "R33") (pin "2") (pinfunction "2_2") (pintype "passive"))
    )
    (net (code "52") (name "Net-(J4-2)") (class "Default")
      (node (ref "J4") (pin "PWM") (pinfunction "2_PWM") (pintype "bidirectional"))
      (node (ref "LED7") (pin "C") (pinfunction "C_C") (pintype "passive"))
      (node (ref "Q5") (pin "2") (pinfunction "D_2") (pintype "passive"))
    )
    (net (code "53") (name "Net-(J4-3)") (class "Default")
      (node (ref "J4") (pin "I/O") (pinfunction "3_I/O") (pintype "bidirectional"))
      (node (ref "R34") (pin "2") (pinfunction "2_2") (pintype "passive"))
    )
    (net (code "54") (name "Net-(J5-2)") (class "Default")
      (node (ref "J5") (pin "PWM") (pinfunction "2_PWM") (pintype "bidirectional"))
      (node (ref "LED8") (pin "C") (pinfunction "C_C") (pintype "passive"))
      (node (ref "Q6") (pin "2") (pinfunction "D_2") (pintype "passive"))
    )
    (net (code "55") (name "Net-(J5-3)") (class "Default")
      (node (ref "J5") (pin "I/O") (pinfunction "3_I/O") (pintype "bidirectional"))
      (node (ref "R35") (pin "2") (pinfunction "2_2") (pintype "passive"))
    )
    (net (code "56") (name "Net-(J7B-S)") (class "Default")
      (node (ref "J7") (pin "2") (pinfunction "S_2") (pintype "passive"))
      (node (ref "Q7") (pin "2") (pinfunction "D_2") (pintype "passive"))
    )
    (net (code "57") (name "Net-(LED1-PadA)") (class "Default")
      (node (ref "LED1") (pin "A") (pinfunction "A_A") (pintype "passive"))
      (node (ref "RL5") (pin "2") (pinfunction "2_2") (pintype "passive"))
    )
    (net (code "58") (name "Net-(LED2-PadA)") (class "Default")
      (node (ref "LED2") (pin "A") (pinfunction "A_A") (pintype "passive"))
      (node (ref "R25") (pin "1") (pinfunction "1_1") (pintype "passive"))
    )
    (net (code "59") (name "Net-(LED3-PadA)") (class "Default")
      (node (ref "LED3") (pin "A") (pinfunction "A_A") (pintype "passive"))
      (node (ref "R27") (pin "1") (pinfunction "1_1") (pintype "passive"))
    )
    (net (code "60") (name "Net-(LED4-PadA)") (class "Default")
      (node (ref "LED4") (pin "A") (pinfunction "A_A") (pintype "passive"))
      (node (ref "RL4") (pin "2") (pinfunction "2_2") (pintype "passive"))
    )
    (net (code "61") (name "Net-(LED5-PadA)") (class "Default")
      (node (ref "LED5") (pin "A") (pinfunction "A_A") (pintype "passive"))
      (node (ref "R4") (pin "1") (pinfunction "1_1") (pintype "passive"))
    )
    (net (code "62") (name "Net-(LED6-PadA)") (class "Default")
      (node (ref "LED6") (pin "A") (pinfunction "A_A") (pintype "passive"))
      (node (ref "R5") (pin "1") (pinfunction "1_1") (pintype "passive"))
    )
    (net (code "63") (name "Net-(LED7-PadA)") (class "Default")
      (node (ref "LED7") (pin "A") (pinfunction "A_A") (pintype "passive"))
      (node (ref "R6") (pin "1") (pinfunction "1_1") (pintype "passive"))
    )
    (net (code "64") (name "Net-(LED8-PadA)") (class "Default")
      (node (ref "LED8") (pin "A") (pinfunction "A_A") (pintype "passive"))
      (node (ref "R7") (pin "1") (pinfunction "1_1") (pintype "passive"))
    )
    (net (code "65") (name "Net-(LED9-PadA)") (class "Default")
      (node (ref "LED9") (pin "A") (pinfunction "A_A") (pintype "passive"))
      (node (ref "R12") (pin "1") (pinfunction "1_1") (pintype "passive"))
    )
    (net (code "66") (name "Net-(LED9-PadC)") (class "Default")
      (node (ref "LED9") (pin "C") (pinfunction "C_C") (pintype "passive"))
      (node (ref "U$3") (pin "RNU") (pinfunction "RNU_RNU") (pintype "bidirectional"))
    )
    (net (code "67") (name "Net-(LED10-PadA)") (class "Default")
      (node (ref "LED10") (pin "A") (pinfunction "A_A") (pintype "passive"))
      (node (ref "RL3") (pin "1") (pinfunction "1_1") (pintype "passive"))
    )
    (net (code "68") (name "Net-(LED11-PadA)") (class "Default")
      (node (ref "LED11") (pin "A") (pinfunction "A_A") (pintype "passive"))
      (node (ref "R14") (pin "1") (pinfunction "1_1") (pintype "passive"))
    )
    (net (code "69") (name "Net-(LED11-PadC)") (class "Default")
      (node (ref "LED11") (pin "C") (pinfunction "C_C") (pintype "passive"))
      (node (ref "U$3") (pin "NET") (pinfunction "NET_NET") (pintype "bidirectional"))
    )
    (net (code "70") (name "Net-(LED12-PadA)") (class "Default")
      (node (ref "LED12") (pin "A") (pinfunction "A_A") (pintype "passive"))
      (node (ref "R39") (pin "1") (pinfunction "1_1") (pintype "passive"))
    )
    (net (code "71") (name "Net-(LED12-PadC)") (class "Default")
      (node (ref "LED12") (pin "C") (pinfunction "C_C") (pintype "passive"))
      (node (ref "U$3") (pin "ALM") (pinfunction "ALM_ALM") (pintype "bidirectional"))
    )
    (net (code "72") (name "Net-(LED13-PadA)") (class "Default")
      (node (ref "LED13") (pin "A") (pinfunction "A_A") (pintype "passive"))
      (node (ref "RL1") (pin "2") (pinfunction "2_2") (pintype "passive"))
    )
    (net (code "73") (name "Net-(LED14-PadA)") (class "Default")
      (node (ref "LED14") (pin "A") (pinfunction "A_A") (pintype "passive"))
      (node (ref "RL7") (pin "2") (pinfunction "2_2") (pintype "passive"))
    )
    (net (code "74") (name "Net-(Q7-G)") (class "Default")
      (node (ref "Q7") (pin "1") (pinfunction "G_1") (pintype "passive"))
      (node (ref "RL2") (pin "2") (pinfunction "2_2") (pintype "passive"))
    )
    (net (code "75") (name "Net-(R8-Pad2)") (class "Default")
      (node (ref "R8") (pin "2") (pinfunction "2_2") (pintype "passive"))
      (node (ref "U$3") (pin "TX1") (pinfunction "TX1_TX1") (pintype "bidirectional"))
    )
    (net (code "76") (name "Net-(R11-Pad2)") (class "Default")
      (node (ref "R11") (pin "2") (pinfunction "2_2") (pintype "passive"))
      (node (ref "U$3") (pin "RX1") (pinfunction "RX1_RX1") (pintype "bidirectional"))
    )
    (net (code "77") (name "Net-(R18-Pad2)") (class "Default")
      (node (ref "R18") (pin "2") (pinfunction "2_2") (pintype "passive"))
      (node (ref "U$1") (pin "SCK") (pinfunction "SCK_SCK") (pintype "bidirectional"))
    )
    (net (code "78") (name "Net-(R24-Pad2)") (class "Default")
      (node (ref "R24") (pin "2") (pinfunction "2_2") (pintype "passive"))
      (node (ref "X4") (pin "3") (pinfunction "3_3") (pintype "passive"))
    )
    (net (code "79") (name "Net-(R31-Pad2)") (class "Default")
      (node (ref "R31") (pin "2") (pinfunction "2_2") (pintype "passive"))
      (node (ref "X4") (pin "2") (pinfunction "2_2") (pintype "passive"))
    )
    (net (code "80") (name "Net-(U$1-CS)") (class "Default")
      (node (ref "R16") (pin "1") (pinfunction "1_1") (pintype "passive"))
      (node (ref "R17") (pin "1") (pinfunction "1_1") (pintype "passive"))
      (node (ref "U$1") (pin "CE") (pinfunction "CS_CE") (pintype "bidirectional"))
    )
    (net (code "81") (name "Net-(U$4-UCAP)") (class "Default")
      (node (ref "C3") (pin "2") (pinfunction "2_2") (pintype "passive"))
      (node (ref "U$4") (pin "6") (pinfunction "UCAP_6") (pintype "bidirectional"))
    )
    (net (code "82") (name "Net-(X2B-S)") (class "Default")
      (node (ref "R10") (pin "2") (pinfunction "2_2") (pintype "passive"))
      (node (ref "RL6") (pin "2") (pinfunction "2_2") (pintype "passive"))
      (node (ref "X2") (pin "2") (pinfunction "S_2") (pintype "passive"))
    )
    (net (code "83") (name "Net-(X5B-S)") (class "Default")
      (node (ref "R21") (pin "2") (pinfunction "2_2") (pintype "passive"))
      (node (ref "RL8") (pin "2") (pinfunction "2_2") (pintype "passive"))
      (node (ref "X5") (pin "2") (pinfunction "S_2") (pintype "passive"))
    )
    (net (code "84") (name "VUSB") (class "Default")
      (node (ref "C7") (pin "2") (pinfunction "2_2") (pintype "passive"))
      (node (ref "D4") (pin "A") (pinfunction "A_A") (pintype "passive"))
      (node (ref "U$4") (pin "7") (pinfunction "VBUS_7") (pintype "bidirectional"))
      (node (ref "X4") (pin "1") (pinfunction "1_1") (pintype "passive"))
    )
    (net (code "85") (name "unconnected-(CFG-Pad2)") (class "Default")
      (node (ref "CFG") (pin "2") (pinfunction "2_2") (pintype "passive"))
    )
    (net (code "86") (name "unconnected-(CFG-Pad3)") (class "Default")
      (node (ref "CFG") (pin "3") (pinfunction "3_3") (pintype "passive"))
    )
    (net (code "87") (name "unconnected-(Q1-D-Pad4)") (class "Default")
      (node (ref "Q1") (pin "4") (pinfunction "D_4") (pintype "passive"))
    )
    (net (code "88") (name "unconnected-(Q2-D-Pad4)") (class "Default")
      (node (ref "Q2") (pin "4") (pinfunction "D_4") (pintype "passive"))
    )
    (net (code "89") (name "unconnected-(Q4-D-Pad4)") (class "Default")
      (node (ref "Q4") (pin "4") (pinfunction "D_4") (pintype "passive"))
    )
    (net (code "90") (name "unconnected-(Q5-D-Pad4)") (class "Default")
      (node (ref "Q5") (pin "4") (pinfunction "D_4") (pintype "passive"))
    )
    (net (code "91") (name "unconnected-(Q6-D-Pad4)") (class "Default")
      (node (ref "Q6") (pin "4") (pinfunction "D_4") (pintype "passive"))
    )
    (net (code "92") (name "unconnected-(RESET1-Pad1)") (class "Default")
      (node (ref "RESET1") (pin "1") (pinfunction "1_1") (pintype "passive"))
    )
    (net (code "93") (name "unconnected-(RESET1-Pad3)") (class "Default")
      (node (ref "RESET1") (pin "3") (pinfunction "3_3") (pintype "passive"))
    )
    (net (code "94") (name "unconnected-(U$3-PadRST)") (class "Default")
      (node (ref "U$3") (pin "RST") (pinfunction "RST_RST") (pintype "bidirectional"))
    )
    (net (code "95") (name "unconnected-(X4-Pad4)") (class "Default")
      (node (ref "X4") (pin "4") (pinfunction "4_4") (pintype "passive"))
    )
  )
)
